# INA260_TB.net
KiCad netlist of a schematic drawn in EAGLE
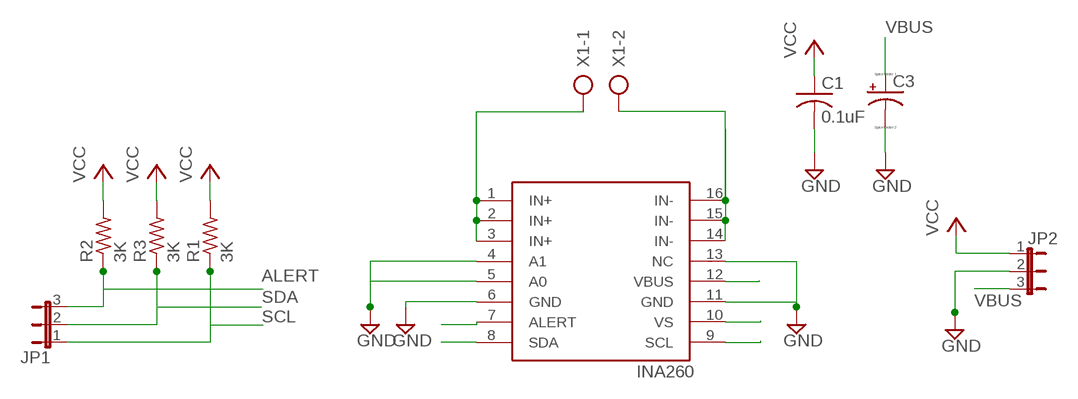
[diagram p0: schematic, sheet 1]

(export (version "E")
  (design (tool "Eeschema 10.0.6"))
  (components
    (comp (ref "C1")
      (value "0.1uF")
      (footprint "eagle-import:C050-025X075")
      (libsource (lib "eagle-import") (part "C-US050-025X075"))
    )
    (comp (ref "C3")
      (value "CPOL-USE5-10.5")
      (footprint "eagle-import:E5-10,5")
      (libsource (lib "eagle-import") (part "CPOL-USE5-10.5"))
    )
    (comp (ref "JP1")
      (value "JP2E")
      (footprint "eagle-import:JP2")
      (libsource (lib "eagle-import") (part "JP2E"))
    )
    (comp (ref "JP2")
      (value "JP2E")
      (footprint "eagle-import:JP2")
      (libsource (lib "eagle-import") (part "JP2E"))
    )
    (comp (ref "R1")
      (value "3K")
      (footprint "eagle-import:0207_10")
      (libsource (lib "eagle-import") (part "R-US_0207/10"))
    )
    (comp (ref "R2")
      (value "3K")
      (footprint "eagle-import:0207_10")
      (libsource (lib "eagle-import") (part "R-US_0207/10"))
    )
    (comp (ref "R3")
      (value "3K")
      (footprint "eagle-import:0207_10")
      (libsource (lib "eagle-import") (part "R-US_0207/10"))
    )
    (comp (ref "U$1")
      (value "INA260")
      (footprint "eagle-import:TSSOP16")
      (fields (field (name "MANUFACTURER") "Texas Instruments"))
      (libsource (lib "eagle-import") (part "INA260"))
    )
    (comp (ref "X1")
      (value "AK300/2")
      (footprint "eagle-import:AK300_2")
      (libsource (lib "eagle-import") (part "AK300/2"))
    )
  )
  (nets
    (net (code "1") (name "/ALERT") (class "Default")
      (node (ref "JP1") (pin "3") (pinfunction "3_3") (pintype "passive"))
      (node (ref "R2") (pin "1") (pinfunction "1_1") (pintype "passive"))
      (node (ref "U$1") (pin "7") (pinfunction "ALERT_7") (pintype "output"))
    )
    (net (code "2") (name "/SCL") (class "Default")
      (node (ref "JP1") (pin "1") (pinfunction "1_1") (pintype "passive"))
      (node (ref "R1") (pin "1") (pinfunction "1_1") (pintype "passive"))
      (node (ref "U$1") (pin "9") (pinfunction "SCL_9") (pintype "input"))
    )
    (net (code "3") (name "/SDA") (class "Default")
      (node (ref "JP1") (pin "2") (pinfunction "2_2") (pintype "passive"))
      (node (ref "R3") (pin "1") (pinfunction "1_1") (pintype "passive"))
      (node (ref "U$1") (pin "8") (pinfunction "SDA_8") (pintype "bidirectional"))
    )
    (net (code "4") (name "/VBUS") (class "Default")
      (node (ref "C3") (pin "+") (pinfunction "+_+") (pintype "passive"))
      (node (ref "JP2") (pin "3") (pinfunction "3_3") (pintype "passive"))
      (node (ref "U$1") (pin "12") (pinfunction "VBUS_12") (pintype "input"))
    )
    (net (code "5") (name "GND") (class "Default")
      (node (ref "C1") (pin "2") (pinfunction "2_2") (pintype "passive"))
      (node (ref "C3") (pin "-") (pinfunction "-_-") (pintype "passive"))
      (node (ref "JP2") (pin "2") (pinfunction "2_2") (pintype "passive"))
      (node (ref "U$1") (pin "11") (pinfunction "GND_11") (pintype "power_in"))
      (node (ref "U$1") (pin "13") (pinfunction "NC_13") (pintype "bidirectional"))
      (node (ref "U$1") (pin "4") (pinfunction "A1_4") (pintype "input"))
      (node (ref "U$1") (pin "5") (pinfunction "A0_5") (pintype "input"))
      (node (ref "U$1") (pin "6") (pinfunction "GND_6") (pintype "power_in"))
    )
    (net (code "6") (name "Net-(X1A-KL)") (class "Default")
      (node (ref "U$1") (pin "1") (pinfunction "IN+_1") (pintype "input"))
      (node (ref "U$1") (pin "2") (pinfunction "IN+_2") (pintype "input"))
      (node (ref "U$1") (pin "3") (pinfunction "IN+_3") (pintype "input"))
      (node (ref "X1") (pin "1") (pinfunction "KL_1") (pintype "passive"))
    )
    (net (code "7") (name "Net-(X1B-KL)") (class "Default")
      (node (ref "U$1") (pin "14") (pinfunction "IN-_14") (pintype "input"))
      (node (ref "U$1") (pin "15") (pinfunction "IN-_15") (pintype "input"))
      (node (ref "U$1") (pin "16") (pinfunction "IN-_16") (pintype "input"))
      (node (ref "X1") (pin "2") (pinfunction "KL_2") (pintype "passive"))
    )
    (net (code "8") (name "VCC") (class "Default")
      (node (ref "C1") (pin "1") (pinfunction "1_1") (pintype "passive"))
      (node (ref "JP2") (pin "1") (pinfunction "1_1") (pintype "passive"))
      (node (ref "R1") (pin "2") (pinfunction "2_2") (pintype "passive"))
      (node (ref "R2") (pin "2") (pinfunction "2_2") (pintype "passive"))
      (node (ref "R3") (pin "2") (pinfunction "2_2") (pintype "passive"))
      (node (ref "U$1") (pin "10") (pinfunction "VS_10") (pintype "power_in"))
    )
  )
)
